# CAN_Termination_Connector.net
KiCad netlist of a schematic drawn in Altium Designer
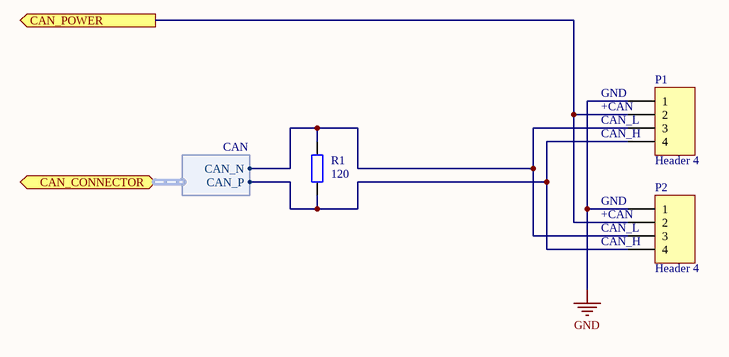
[diagram p0: CAN Termination Connector.SchDoc]

(export (version "E")
  (design (tool "Eeschema 10.0.6"))
  (components
    (comp (ref "P1")
      (value "Header 4")
      (footprint "87437-0443")
      (description "Header, 4-Pin")
      (fields (field (name "PUBLISHER") "Altium Limited"))
      (libsource (lib "Miscellaneous Connectors") (part "Header 4"))
    )
    (comp (ref "P2")
      (value "Header 4")
      (footprint "87437-0443")
      (description "Header, 4-Pin")
      (fields (field (name "PUBLISHER") "Altium Limited"))
      (libsource (lib "Miscellaneous Connectors") (part "Header 4"))
    )
    (comp (ref "R1")
      (value "120")
      (footprint "R0603")
      (description "Resistor")
      (fields (field (name "Comment") "Res2") (field (name "PUBLISHER") "Altium Limited"))
      (libsource (lib "Miscellaneous Devices") (part "Res2"))
    )
  )
  (nets
    (net (code "2") (name "/CAN_POWER") (class "Default")
      (node (ref "P1") (pin "2") (pinfunction "2_2") (pintype "passive"))
      (node (ref "P2") (pin "2") (pinfunction "2_2") (pintype "passive"))
    )
    (net (code "4") (name "GND") (class "Default")
      (node (ref "P1") (pin "1") (pinfunction "1_1") (pintype "passive"))
      (node (ref "P2") (pin "1") (pinfunction "1_1") (pintype "passive"))
    )
    (net (code "5") (name "Net-(P1-Pad3)") (class "Default")
      (node (ref "P1") (pin "3") (pinfunction "3_3") (pintype "passive"))
      (node (ref "P2") (pin "3") (pinfunction "3_3") (pintype "passive"))
      (node (ref "R1") (pin "2") (pinfunction "2_2") (pintype "passive"))
    )
    (net (code "6") (name "Net-(P1-Pad4)") (class "Default")
      (node (ref "P1") (pin "4") (pinfunction "4_4") (pintype "passive"))
      (node (ref "P2") (pin "4") (pinfunction "4_4") (pintype "passive"))
      (node (ref "R1") (pin "1") (pinfunction "1_1") (pintype "passive"))
    )
  )
)
